# Primary_Board.net
KiCad netlist of a schematic drawn in EAGLE
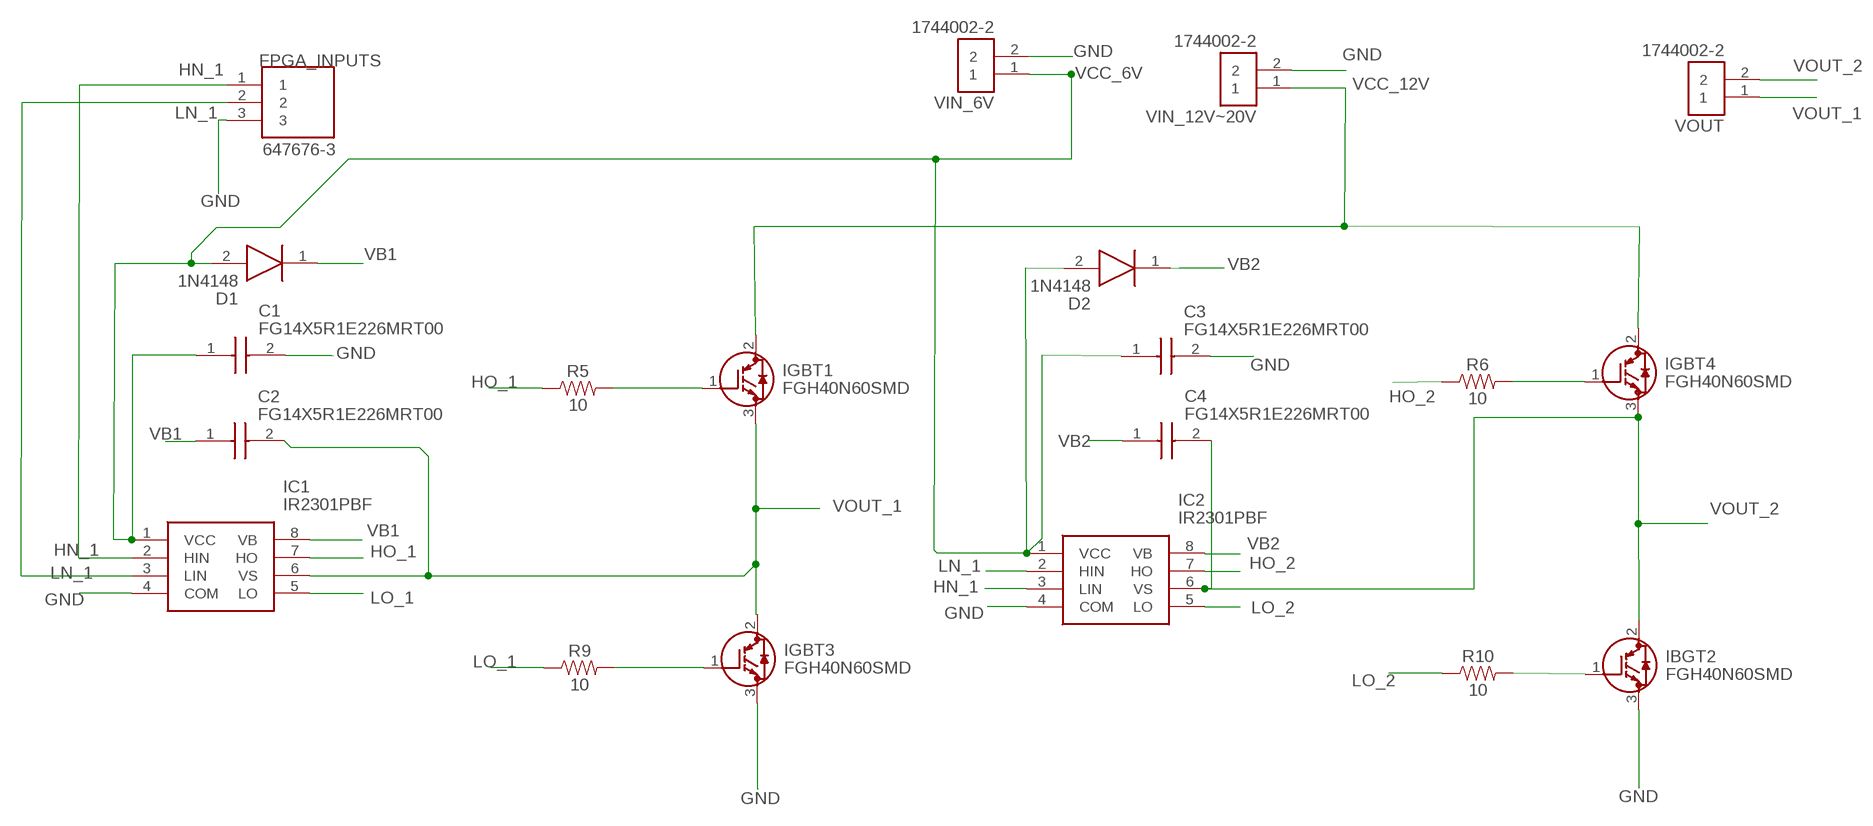
[diagram p0: schematic, sheet 1]

(export (version "E")
  (design (tool "Eeschema 10.0.6"))
  (components
    (comp (ref "C1")
      (value "FG14X5R1E226MRT00")
      (footprint "eagle-import:CAPPRD550W50D395H550")
      (libsource (lib "eagle-import") (part "FG14X5R1E226MRT00"))
    )
    (comp (ref "C2")
      (value "FG14X5R1E226MRT00")
      (footprint "eagle-import:CAPPRD550W50D395H550")
      (libsource (lib "eagle-import") (part "FG14X5R1E226MRT00"))
    )
    (comp (ref "C3")
      (value "FG14X5R1E226MRT00")
      (footprint "eagle-import:CAPPRD550W50D395H550")
      (libsource (lib "eagle-import") (part "FG14X5R1E226MRT00"))
    )
    (comp (ref "C4")
      (value "FG14X5R1E226MRT00")
      (footprint "eagle-import:CAPPRD550W50D395H550")
      (libsource (lib "eagle-import") (part "FG14X5R1E226MRT00"))
    )
    (comp (ref "D1")
      (value "1N4148")
      (footprint "eagle-import:DIOAD1068W53L380D172")
      (fields (field (name "MOUSER_PART_NUMBER") "512-1N4148") (field (name "RS_PART_NUMBER") "1698781"))
      (libsource (lib "eagle-import") (part "1N4148"))
    )
    (comp (ref "D2")
      (value "1N4148")
      (footprint "eagle-import:DIOAD1068W53L380D172")
      (fields (field (name "MOUSER_PART_NUMBER") "512-1N4148") (field (name "RS_PART_NUMBER") "1698781"))
      (libsource (lib "eagle-import") (part "1N4148"))
    )
    (comp (ref "FPGA_INPUTS")
      (value "647676-3")
      (footprint "eagle-import:TE_647676-3")
      (fields (field (name "MF") "TE Connectivity"))
      (libsource (lib "eagle-import") (part "647676-3"))
    )
    (comp (ref "IBGT2")
      (value "FGH40N60SMD")
      (footprint "eagle-import:TO556P482X1562X2475-3P")
      (fields (field (name "MOUSER_PART_NUMBER") "512-FGH40N60SMD") (field (name "RS_PART_NUMBER") "1241336"))
      (libsource (lib "eagle-import") (part "FGH40N60SMD"))
    )
    (comp (ref "IC1")
      (value "IR2301PBF")
      (footprint "eagle-import:DIP762W56P254L988H533Q8N")
      (fields (field (name "MOUSER_PART_NUMBER") "942-IR2301PBF") (field (name "RS_PART_NUMBER") "8655724P"))
      (libsource (lib "eagle-import") (part "IR2301PBF"))
    )
    (comp (ref "IC2")
      (value "IR2301PBF")
      (footprint "eagle-import:DIP762W56P254L988H533Q8N")
      (fields (field (name "MOUSER_PART_NUMBER") "942-IR2301PBF") (field (name "RS_PART_NUMBER") "8655724P"))
      (libsource (lib "eagle-import") (part "IR2301PBF"))
    )
    (comp (ref "IGBT1")
      (value "FGH40N60SMD")
      (footprint "eagle-import:TO556P482X1562X2475-3P")
      (fields (field (name "MOUSER_PART_NUMBER") "512-FGH40N60SMD") (field (name "RS_PART_NUMBER") "1241336"))
      (libsource (lib "eagle-import") (part "FGH40N60SMD"))
    )
    (comp (ref "IGBT3")
      (value "FGH40N60SMD")
      (footprint "eagle-import:TO556P482X1562X2475-3P")
      (fields (field (name "MOUSER_PART_NUMBER") "512-FGH40N60SMD") (field (name "RS_PART_NUMBER") "1241336"))
      (libsource (lib "eagle-import") (part "FGH40N60SMD"))
    )
    (comp (ref "IGBT4")
      (value "FGH40N60SMD")
      (footprint "eagle-import:TO556P482X1562X2475-3P")
      (fields (field (name "MOUSER_PART_NUMBER") "512-FGH40N60SMD") (field (name "RS_PART_NUMBER") "1241336"))
      (libsource (lib "eagle-import") (part "FGH40N60SMD"))
    )
    (comp (ref "R5")
      (value "10")
      (footprint "eagle-import:AXIAL-0.3")
      (libsource (lib "eagle-import") (part "10OHM-HORIZ-1/4W-1%"))
    )
    (comp (ref "R6")
      (value "10")
      (footprint "eagle-import:AXIAL-0.3")
      (libsource (lib "eagle-import") (part "10OHM-HORIZ-1/4W-1%"))
    )
    (comp (ref "R9")
      (value "10")
      (footprint "eagle-import:AXIAL-0.3")
      (libsource (lib "eagle-import") (part "10OHM-HORIZ-1/4W-1%"))
    )
    (comp (ref "R10")
      (value "10")
      (footprint "eagle-import:AXIAL-0.3")
      (libsource (lib "eagle-import") (part "10OHM-HORIZ-1/4W-1%"))
    )
    (comp (ref "VIN_6V")
      (value "1744002-2")
      (footprint "eagle-import:CONN_1744002-2")
      (fields (field (name "MF") "TE Connectivity"))
      (libsource (lib "eagle-import") (part "1744002-2"))
    )
    (comp (ref "VIN_12V~20V")
      (value "1744002-2")
      (footprint "eagle-import:CONN_1744002-2")
      (fields (field (name "MF") "TE Connectivity"))
      (libsource (lib "eagle-import") (part "1744002-2"))
    )
    (comp (ref "VOUT")
      (value "1744002-2")
      (footprint "eagle-import:CONN_1744002-2")
      (fields (field (name "MF") "TE Connectivity"))
      (libsource (lib "eagle-import") (part "1744002-2"))
    )
  )
  (nets
    (net (code "1") (name "/GND") (class "Default")
      (node (ref "C1") (pin "2") (pinfunction "-_2") (pintype "bidirectional"))
      (node (ref "C3") (pin "2") (pinfunction "-_2") (pintype "bidirectional"))
      (node (ref "FPGA_INPUTS") (pin "3") (pinfunction "3_3") (pintype "passive"))
      (node (ref "IBGT2") (pin "3") (pinfunction "E_3") (pintype "bidirectional"))
      (node (ref "IC1") (pin "4") (pinfunction "COM_4") (pintype "bidirectional"))
      (node (ref "IC2") (pin "4") (pinfunction "COM_4") (pintype "bidirectional"))
      (node (ref "IGBT3") (pin "3") (pinfunction "E_3") (pintype "bidirectional"))
      (node (ref "VIN_12V~20V") (pin "2") (pinfunction "2_2") (pintype "passive"))
      (node (ref "VIN_6V") (pin "2") (pinfunction "2_2") (pintype "passive"))
    )
    (net (code "2") (name "/HN_1") (class "Default")
      (node (ref "FPGA_INPUTS") (pin "1") (pinfunction "1_1") (pintype "passive"))
      (node (ref "IC1") (pin "2") (pinfunction "HIN_2") (pintype "bidirectional"))
      (node (ref "IC2") (pin "3") (pinfunction "LIN_3") (pintype "bidirectional"))
    )
    (net (code "3") (name "/HO_1") (class "Default")
      (node (ref "IC1") (pin "7") (pinfunction "HO_7") (pintype "bidirectional"))
      (node (ref "R5") (pin "P$1") (pinfunction "1_P$1") (pintype "passive"))
    )
    (net (code "4") (name "/HO_2") (class "Default")
      (node (ref "IC2") (pin "7") (pinfunction "HO_7") (pintype "bidirectional"))
      (node (ref "R6") (pin "P$1") (pinfunction "1_P$1") (pintype "passive"))
    )
    (net (code "5") (name "/LN_1") (class "Default")
      (node (ref "FPGA_INPUTS") (pin "2") (pinfunction "2_2") (pintype "passive"))
      (node (ref "IC1") (pin "3") (pinfunction "LIN_3") (pintype "bidirectional"))
      (node (ref "IC2") (pin "2") (pinfunction "HIN_2") (pintype "bidirectional"))
    )
    (net (code "6") (name "/LO_1") (class "Default")
      (node (ref "IC1") (pin "5") (pinfunction "LO_5") (pintype "bidirectional"))
      (node (ref "R9") (pin "P$1") (pinfunction "1_P$1") (pintype "passive"))
    )
    (net (code "7") (name "/LO_2") (class "Default")
      (node (ref "IC2") (pin "5") (pinfunction "LO_5") (pintype "bidirectional"))
      (node (ref "R10") (pin "P$1") (pinfunction "1_P$1") (pintype "passive"))
    )
    (net (code "8") (name "/VB1") (class "Default")
      (node (ref "C2") (pin "1") (pinfunction "+_1") (pintype "bidirectional"))
      (node (ref "D1") (pin "1") (pinfunction "K_1") (pintype "bidirectional"))
      (node (ref "IC1") (pin "8") (pinfunction "VB_8") (pintype "bidirectional"))
    )
    (net (code "9") (name "/VB2") (class "Default")
      (node (ref "C4") (pin "1") (pinfunction "+_1") (pintype "bidirectional"))
      (node (ref "D2") (pin "1") (pinfunction "K_1") (pintype "bidirectional"))
      (node (ref "IC2") (pin "8") (pinfunction "VB_8") (pintype "bidirectional"))
    )
    (net (code "10") (name "/VCC_6V") (class "Default")
      (node (ref "C1") (pin "1") (pinfunction "+_1") (pintype "bidirectional"))
      (node (ref "C3") (pin "1") (pinfunction "+_1") (pintype "bidirectional"))
      (node (ref "D1") (pin "2") (pinfunction "A_2") (pintype "bidirectional"))
      (node (ref "D2") (pin "2") (pinfunction "A_2") (pintype "bidirectional"))
      (node (ref "IC1") (pin "1") (pinfunction "VCC_1") (pintype "bidirectional"))
      (node (ref "IC2") (pin "1") (pinfunction "VCC_1") (pintype "bidirectional"))
      (node (ref "VIN_6V") (pin "1") (pinfunction "1_1") (pintype "passive"))
    )
    (net (code "11") (name "/VCC_12V") (class "Default")
      (node (ref "IGBT1") (pin "2") (pinfunction "C_2") (pintype "bidirectional"))
      (node (ref "IGBT4") (pin "2") (pinfunction "C_2") (pintype "bidirectional"))
      (node (ref "VIN_12V~20V") (pin "1") (pinfunction "1_1") (pintype "passive"))
    )
    (net (code "12") (name "/VOUT_1") (class "Default")
      (node (ref "C2") (pin "2") (pinfunction "-_2") (pintype "bidirectional"))
      (node (ref "IC1") (pin "6") (pinfunction "VS_6") (pintype "bidirectional"))
      (node (ref "IGBT1") (pin "3") (pinfunction "E_3") (pintype "bidirectional"))
      (node (ref "IGBT3") (pin "2") (pinfunction "C_2") (pintype "bidirectional"))
      (node (ref "VOUT") (pin "1") (pinfunction "1_1") (pintype "passive"))
    )
    (net (code "13") (name "/VOUT_2") (class "Default")
      (node (ref "C4") (pin "2") (pinfunction "-_2") (pintype "bidirectional"))
      (node (ref "IBGT2") (pin "2") (pinfunction "C_2") (pintype "bidirectional"))
      (node (ref "IC2") (pin "6") (pinfunction "VS_6") (pintype "bidirectional"))
      (node (ref "IGBT4") (pin "3") (pinfunction "E_3") (pintype "bidirectional"))
      (node (ref "VOUT") (pin "2") (pinfunction "2_2") (pintype "passive"))
    )
    (net (code "14") (name "Net-(IBGT2-G)") (class "Default")
      (node (ref "IBGT2") (pin "1") (pinfunction "G_1") (pintype "bidirectional"))
      (node (ref "R10") (pin "P$2") (pinfunction "2_P$2") (pintype "passive"))
    )
    (net (code "15") (name "Net-(IGBT1-G)") (class "Default")
      (node (ref "IGBT1") (pin "1") (pinfunction "G_1") (pintype "bidirectional"))
      (node (ref "R5") (pin "P$2") (pinfunction "2_P$2") (pintype "passive"))
    )
    (net (code "16") (name "Net-(IGBT3-G)") (class "Default")
      (node (ref "IGBT3") (pin "1") (pinfunction "G_1") (pintype "bidirectional"))
      (node (ref "R9") (pin "P$2") (pinfunction "2_P$2") (pintype "passive"))
    )
    (net (code "17") (name "Net-(IGBT4-G)") (class "Default")
      (node (ref "IGBT4") (pin "1") (pinfunction "G_1") (pintype "bidirectional"))
      (node (ref "R6") (pin "P$2") (pinfunction "2_P$2") (pintype "passive"))
    )
  )
)
